# TopBoardLidar.net
KiCad netlist of a schematic drawn in EAGLE
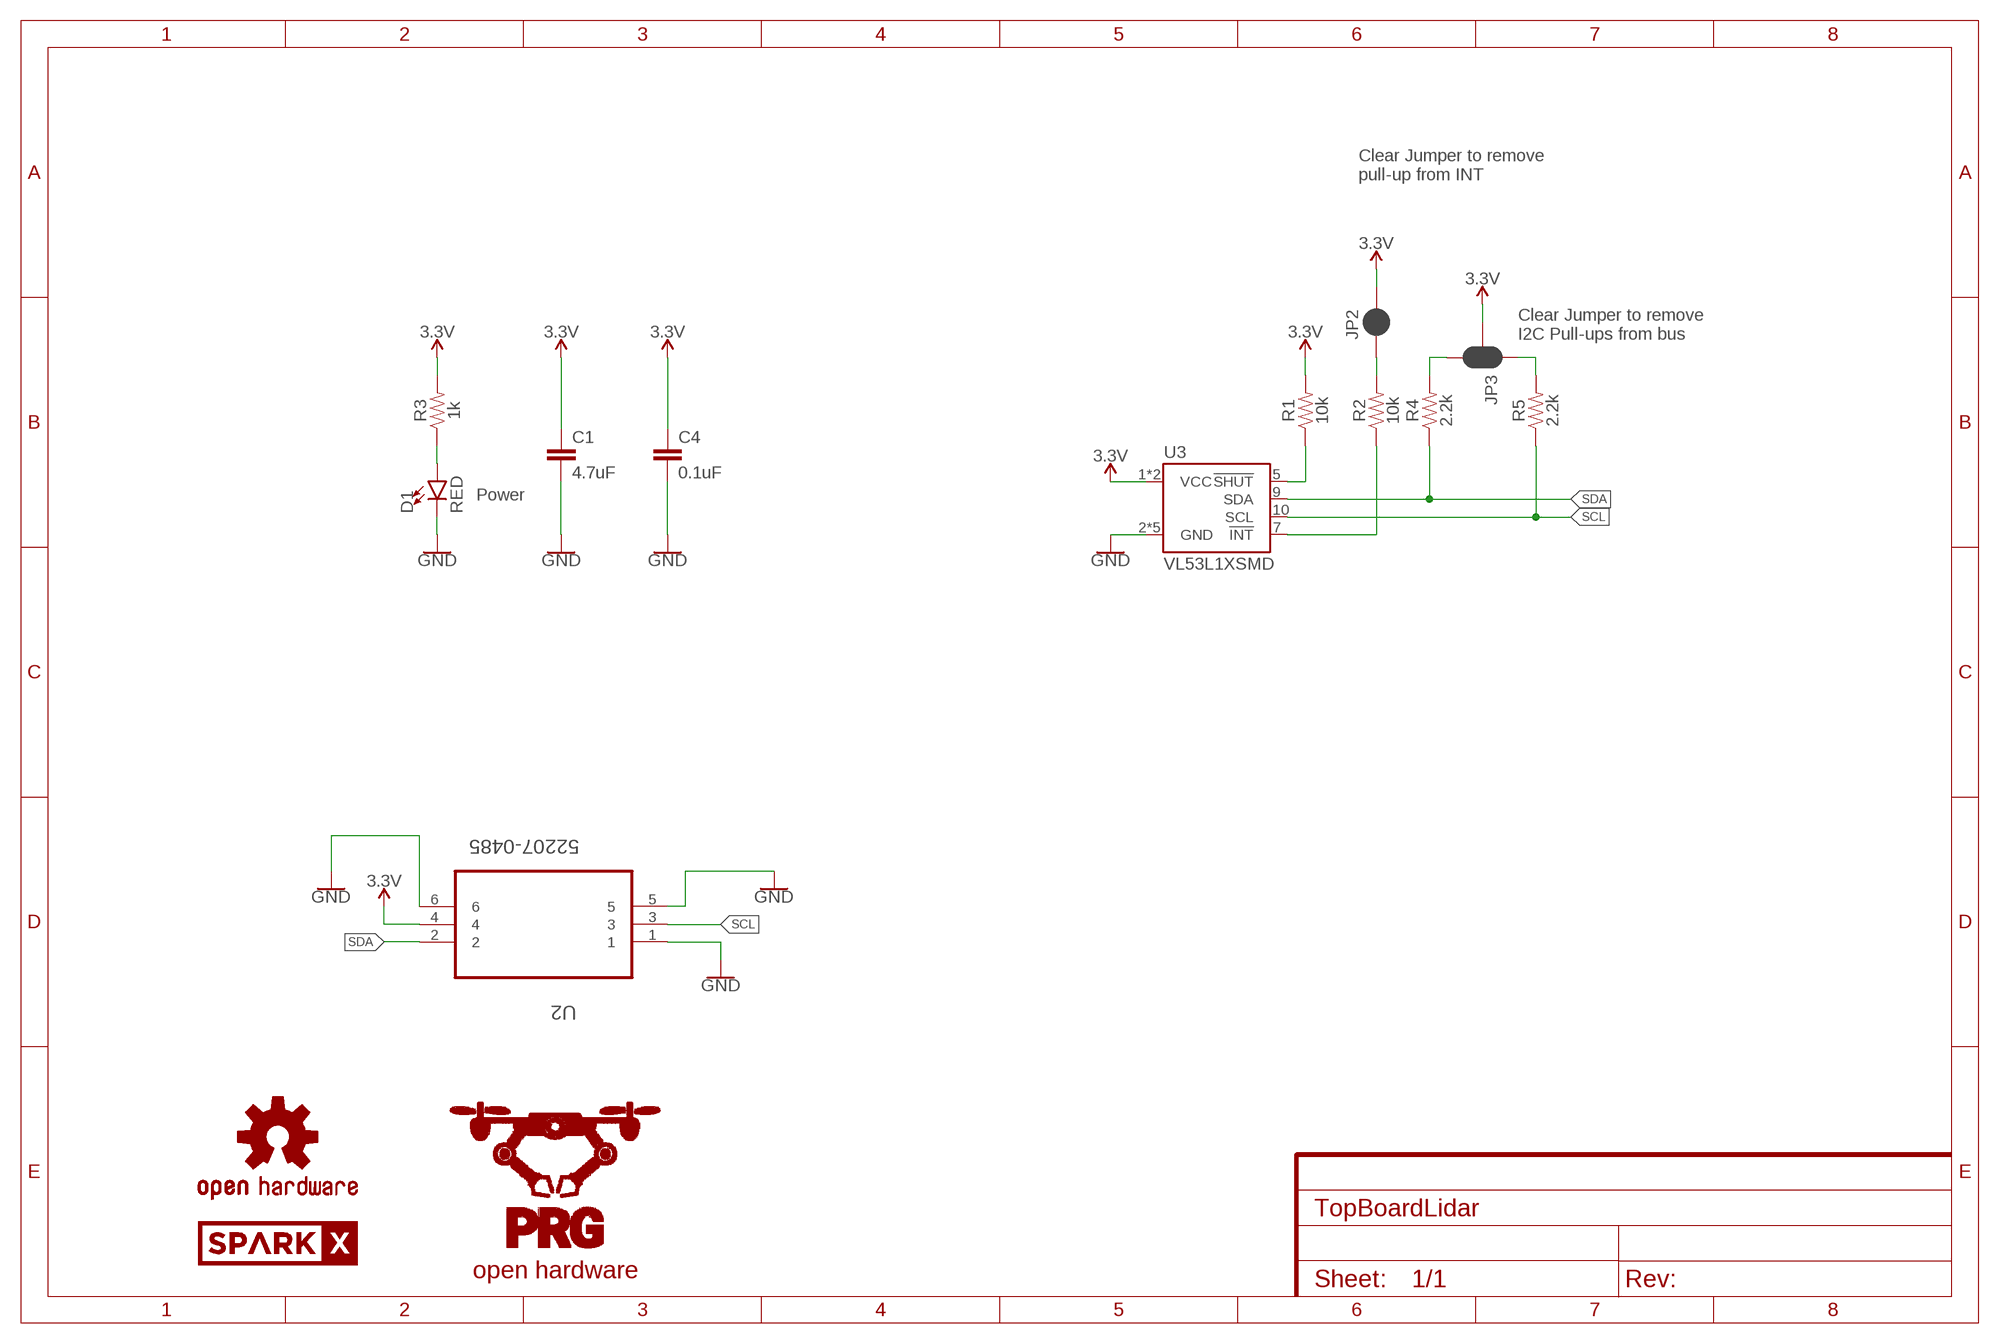
[diagram p0: schematic, sheet 1]

(export (version "E")
  (design (tool "Eeschema 10.0.6"))
  (components
    (comp (ref "C1")
      (value "4.7uF")
      (footprint "eagle-import:0603")
      (libsource (lib "eagle-import") (part "4.7UF0603"))
    )
    (comp (ref "C4")
      (value "0.1uF")
      (footprint "eagle-import:0603")
      (libsource (lib "eagle-import") (part "0.1UF-0603-25V-(+80/-20%)"))
    )
    (comp (ref "D1")
      (value "RED")
      (footprint "eagle-import:LED-0603")
      (libsource (lib "eagle-import") (part "LED-RED0603"))
    )
    (comp (ref "JP2")
      (value "JUMPER-SMT_2_NC_PASTE_NO-SILK")
      (footprint "eagle-import:SMT-JUMPER_2_NC_PASTE_NO-SILK")
      (libsource (lib "eagle-import") (part "JUMPER-SMT_2_NC_PASTE_NO-SILK"))
    )
    (comp (ref "JP3")
      (value "JUMPER-SMT_3_2-NC_PASTE_NO-SILK")
      (footprint "eagle-import:SMT-JUMPER_3_2-NC_PASTE_NO-SILK")
      (libsource (lib "eagle-import") (part "JUMPER-SMT_3_2-NC_PASTE_NO-SILK"))
    )
    (comp (ref "LOGO1")
      (value "OSHW-LOGOMINI")
      (footprint "eagle-import:OSHW-LOGO-MINI")
      (libsource (lib "eagle-import") (part "OSHW-LOGOMINI"))
    )
    (comp (ref "R1")
      (value "10k")
      (footprint "eagle-import:0603")
      (libsource (lib "eagle-import") (part "10KOHM-0603-1/10W-1%"))
    )
    (comp (ref "R2")
      (value "10k")
      (footprint "eagle-import:0603")
      (libsource (lib "eagle-import") (part "10KOHM-0603-1/10W-1%"))
    )
    (comp (ref "R3")
      (value "1k")
      (footprint "eagle-import:0603")
      (libsource (lib "eagle-import") (part "1KOHM-0603-1/10W-1%"))
    )
    (comp (ref "R4")
      (value "2.2k")
      (footprint "eagle-import:0402-TIGHT")
      (libsource (lib "eagle-import") (part "2.2KOHM-0402T-1/16W-1%"))
    )
    (comp (ref "R5")
      (value "2.2k")
      (footprint "eagle-import:0402-TIGHT")
      (libsource (lib "eagle-import") (part "2.2KOHM-0402T-1/16W-1%"))
    )
    (comp (ref "U$1")
      (value "SPARKX-LOGO4")
      (footprint "eagle-import:SPARKX-MEDIUM")
      (libsource (lib "eagle-import") (part "SPARKX-LOGO4"))
    )
    (comp (ref "U$2")
      (value "SPARKX-LOGO4")
      (footprint "eagle-import:SPARKX-MEDIUM")
      (libsource (lib "eagle-import") (part "SPARKX-LOGO4"))
    )
    (comp (ref "U2")
      (value "52207-0485")
      (footprint "eagle-import:MOLEX_52207-0485")
      (libsource (lib "eagle-import") (part "52207-0485"))
    )
    (comp (ref "U3")
      (value "VL53L1XSMD")
      (footprint "eagle-import:VL53L1X")
      (libsource (lib "eagle-import") (part "VL53L1XSMD"))
    )
  )
  (nets
    (net (code "1") (name "3.3V") (class "Default")
      (node (ref "C1") (pin "1") (pinfunction "1_1") (pintype "passive"))
      (node (ref "C4") (pin "1") (pinfunction "1_1") (pintype "passive"))
      (node (ref "JP2") (pin "2") (pinfunction "2_2") (pintype "passive"))
      (node (ref "JP3") (pin "2") (pinfunction "2_2") (pintype "passive"))
      (node (ref "R1") (pin "2") (pinfunction "2_2") (pintype "passive"))
      (node (ref "R3") (pin "2") (pinfunction "2_2") (pintype "passive"))
      (node (ref "U2") (pin "4") (pinfunction "4_4") (pintype "passive"))
      (node (ref "U3") (pin "1") (pinfunction "VCC_1") (pintype "bidirectional"))
      (node (ref "U3") (pin "11") (pinfunction "VCC_11") (pintype "bidirectional"))
    )
    (net (code "2") (name "GND") (class "Default")
      (node (ref "C1") (pin "2") (pinfunction "2_2") (pintype "passive"))
      (node (ref "C4") (pin "2") (pinfunction "2_2") (pintype "passive"))
      (node (ref "D1") (pin "C") (pinfunction "C_C") (pintype "passive"))
      (node (ref "U2") (pin "1") (pinfunction "1_1") (pintype "passive"))
      (node (ref "U2") (pin "5") (pinfunction "5_5") (pintype "passive"))
      (node (ref "U2") (pin "6") (pinfunction "6_6") (pintype "passive"))
      (node (ref "U3") (pin "12") (pinfunction "GND_12") (pintype "bidirectional"))
      (node (ref "U3") (pin "2") (pinfunction "GND_2") (pintype "bidirectional"))
      (node (ref "U3") (pin "3") (pinfunction "GND_3") (pintype "bidirectional"))
      (node (ref "U3") (pin "4") (pinfunction "GND_4") (pintype "bidirectional"))
      (node (ref "U3") (pin "6") (pinfunction "GND_6") (pintype "bidirectional"))
    )
    (net (code "3") (name "Net-(D1-PadA)") (class "Default")
      (node (ref "D1") (pin "A") (pinfunction "A_A") (pintype "passive"))
      (node (ref "R3") (pin "1") (pinfunction "1_1") (pintype "passive"))
    )
    (net (code "4") (name "Net-(JP2-Pad1)") (class "Default")
      (node (ref "JP2") (pin "1") (pinfunction "1_1") (pintype "passive"))
      (node (ref "R2") (pin "2") (pinfunction "2_2") (pintype "passive"))
    )
    (net (code "5") (name "Net-(JP3-Pad1)") (class "Default")
      (node (ref "JP3") (pin "1") (pinfunction "1_1") (pintype "passive"))
      (node (ref "R5") (pin "2") (pinfunction "2_2") (pintype "passive"))
    )
    (net (code "6") (name "Net-(JP3-Pad3)") (class "Default")
      (node (ref "JP3") (pin "3") (pinfunction "3_3") (pintype "passive"))
      (node (ref "R4") (pin "2") (pinfunction "2_2") (pintype "passive"))
    )
    (net (code "7") (name "Net-(U3-~{INT})") (class "Default")
      (node (ref "R2") (pin "1") (pinfunction "1_1") (pintype "passive"))
      (node (ref "U3") (pin "7") (pinfunction "~{INT}_7") (pintype "bidirectional"))
    )
    (net (code "8") (name "Net-(U3-~{SHUT})") (class "Default")
      (node (ref "R1") (pin "1") (pinfunction "1_1") (pintype "passive"))
      (node (ref "U3") (pin "5") (pinfunction "~{SHUT}_5") (pintype "bidirectional"))
    )
    (net (code "9") (name "SCL") (class "Default")
      (node (ref "R5") (pin "1") (pinfunction "1_1") (pintype "passive"))
      (node (ref "U2") (pin "3") (pinfunction "3_3") (pintype "passive"))
      (node (ref "U3") (pin "10") (pinfunction "SCL_10") (pintype "bidirectional"))
    )
    (net (code "10") (name "SDA") (class "Default")
      (node (ref "R4") (pin "1") (pinfunction "1_1") (pintype "passive"))
      (node (ref "U2") (pin "2") (pinfunction "2_2") (pintype "passive"))
      (node (ref "U3") (pin "9") (pinfunction "SDA_9") (pintype "bidirectional"))
    )
  )
)
